# 02_Module.net
KiCad netlist of a schematic drawn in Altium Designer
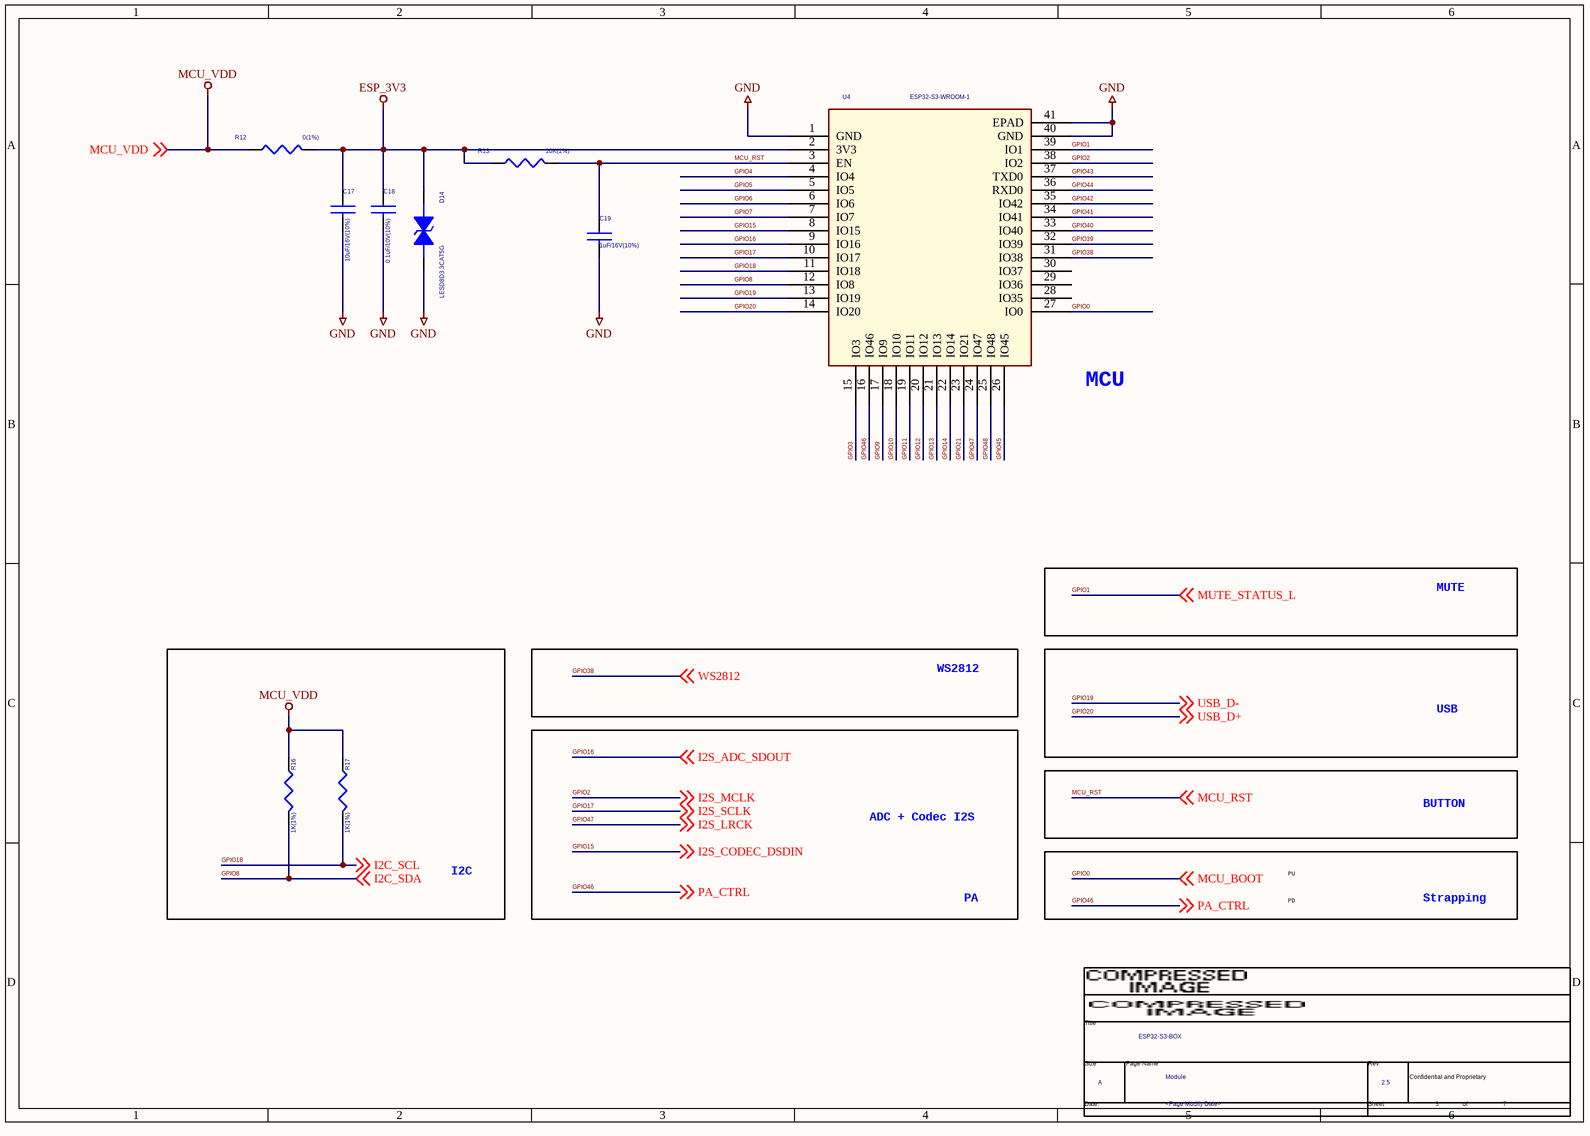
[diagram p0: 02_Module.SchDoc]

(export (version "E")
  (design (tool "Eeschema 10.0.6"))
  (components
    (comp (ref "C17")
      (value "10uF/16V(10%)")
      (footprint "0603_C")
      (fields (field (name "PART NUMBER") "ES11067104600000"))
      (libsource (lib "*") (part "CAPACITOR"))
    )
    (comp (ref "C18")
      (value "0.1uF/10V(10%)")
      (footprint "0402_C")
      (fields (field (name "PART NUMBER") "ES11045103620000"))
      (libsource (lib "*") (part "CAPACITOR"))
    )
    (comp (ref "C19")
      (value "1uF/16V(10%)")
      (footprint "0402_C")
      (fields (field (name "PART NUMBER") "ES11046104610000"))
      (libsource (lib "*") (part "CAPACITOR"))
    )
    (comp (ref "D14")
      (value "LESD8D3.3CAT5G")
      (footprint "SOD-882")
      (fields (field (name "PART NUMBER") "ES31320010000000"))
      (libsource (lib "*") (part "DIODE_BI_DIR"))
    )
    (comp (ref "R12")
      (value "0(1%)")
      (footprint "0603_R")
      (fields (field (name "PART NUMBER") "ES21060000000001"))
      (libsource (lib "*") (part "RESISTOR"))
    )
    (comp (ref "R13")
      (value "10K(1%)")
      (footprint "0402_R")
      (fields (field (name "PART NUMBER") "ES21044100000001"))
      (libsource (lib "*") (part "RESISTOR"))
    )
    (comp (ref "R16")
      (value "1K(1%)")
      (footprint "0201_R")
      (fields (field (name "PART NUMBER") "ES21023100000001"))
      (libsource (lib "*") (part "RESISTOR"))
    )
    (comp (ref "R17")
      (value "1K(1%)")
      (footprint "0201_R")
      (fields (field (name "PART NUMBER") "ES21023100000001"))
      (libsource (lib "*") (part "RESISTOR"))
    )
    (comp (ref "U4")
      (value "ESP32-S3-WROOM-1")
      (footprint "ESP32-S3-WROOM-1")
      (libsource (lib "*") (part "ESP32-S3-WROOM"))
    )
  )
  (nets
    (net (code "1") (name "/GPIO3") (class "Default")
      (node (ref "U4") (pin "15") (pinfunction "IO3_15") (pintype "passive"))
    )
    (net (code "2") (name "/GPIO4") (class "Default")
      (node (ref "U4") (pin "4") (pinfunction "IO4_4") (pintype "passive"))
    )
    (net (code "3") (name "/GPIO5") (class "Default")
      (node (ref "U4") (pin "5") (pinfunction "IO5_5") (pintype "passive"))
    )
    (net (code "4") (name "/GPIO6") (class "Default")
      (node (ref "U4") (pin "6") (pinfunction "IO6_6") (pintype "passive"))
    )
    (net (code "5") (name "/GPIO7") (class "Default")
      (node (ref "U4") (pin "7") (pinfunction "IO7_7") (pintype "passive"))
    )
    (net (code "6") (name "/GPIO9") (class "Default")
      (node (ref "U4") (pin "17") (pinfunction "IO9_17") (pintype "passive"))
    )
    (net (code "7") (name "/GPIO10") (class "Default")
      (node (ref "U4") (pin "18") (pinfunction "IO10_18") (pintype "passive"))
    )
    (net (code "8") (name "/GPIO11") (class "Default")
      (node (ref "U4") (pin "19") (pinfunction "IO11_19") (pintype "passive"))
    )
    (net (code "9") (name "/GPIO12") (class "Default")
      (node (ref "U4") (pin "20") (pinfunction "IO12_20") (pintype "passive"))
    )
    (net (code "10") (name "/GPIO13") (class "Default")
      (node (ref "U4") (pin "21") (pinfunction "IO13_21") (pintype "passive"))
    )
    (net (code "11") (name "/GPIO14") (class "Default")
      (node (ref "U4") (pin "22") (pinfunction "IO14_22") (pintype "passive"))
    )
    (net (code "12") (name "/GPIO21") (class "Default")
      (node (ref "U4") (pin "23") (pinfunction "IO21_23") (pintype "passive"))
    )
    (net (code "13") (name "/GPIO39") (class "Default")
      (node (ref "U4") (pin "32") (pinfunction "IO39_32") (pintype "passive"))
    )
    (net (code "14") (name "/GPIO40") (class "Default")
      (node (ref "U4") (pin "33") (pinfunction "IO40_33") (pintype "passive"))
    )
    (net (code "15") (name "/GPIO41") (class "Default")
      (node (ref "U4") (pin "34") (pinfunction "IO41_34") (pintype "passive"))
    )
    (net (code "16") (name "/GPIO42") (class "Default")
      (node (ref "U4") (pin "35") (pinfunction "IO42_35") (pintype "passive"))
    )
    (net (code "17") (name "/GPIO43") (class "Default")
      (node (ref "U4") (pin "37") (pinfunction "TXD0_37") (pintype "passive"))
    )
    (net (code "18") (name "/GPIO44") (class "Default")
      (node (ref "U4") (pin "36") (pinfunction "RXD0_36") (pintype "passive"))
    )
    (net (code "19") (name "/GPIO45") (class "Default")
      (node (ref "U4") (pin "26") (pinfunction "IO45_26") (pintype "passive"))
    )
    (net (code "20") (name "/GPIO48") (class "Default")
      (node (ref "U4") (pin "25") (pinfunction "IO48_25") (pintype "passive"))
    )
    (net (code "21") (name "ESP_3V3") (class "Default")
      (node (ref "C17") (pin "1") (pinfunction "1_1") (pintype "passive"))
      (node (ref "C18") (pin "1") (pinfunction "1_1") (pintype "passive"))
      (node (ref "D14") (pin "2") (pinfunction "2_2") (pintype "passive"))
      (node (ref "R12") (pin "2") (pinfunction "2_2") (pintype "passive"))
      (node (ref "R13") (pin "1") (pinfunction "1_1") (pintype "passive"))
      (node (ref "U4") (pin "2") (pinfunction "3V3_2") (pintype "power_in"))
    )
    (net (code "22") (name "GND") (class "Default")
      (node (ref "C17") (pin "2") (pinfunction "2_2") (pintype "passive"))
      (node (ref "C18") (pin "2") (pinfunction "2_2") (pintype "passive"))
      (node (ref "C19") (pin "2") (pinfunction "2_2") (pintype "passive"))
      (node (ref "D14") (pin "1") (pinfunction "1_1") (pintype "passive"))
      (node (ref "U4") (pin "1") (pinfunction "GND_1") (pintype "power_in"))
      (node (ref "U4") (pin "40") (pinfunction "GND_40") (pintype "power_in"))
      (node (ref "U4") (pin "41") (pinfunction "EPAD_41") (pintype "power_in"))
    )
    (net (code "23") (name "I2C_SCL") (class "Default")
      (node (ref "R17") (pin "2") (pinfunction "2_2") (pintype "passive"))
      (node (ref "U4") (pin "11") (pinfunction "IO18_11") (pintype "passive"))
    )
    (net (code "24") (name "I2C_SDA") (class "Default")
      (node (ref "R16") (pin "2") (pinfunction "2_2") (pintype "passive"))
      (node (ref "U4") (pin "12") (pinfunction "IO8_12") (pintype "passive"))
    )
    (net (code "25") (name "I2S_ADC_SDOUT") (class "Default")
      (node (ref "U4") (pin "9") (pinfunction "IO16_9") (pintype "passive"))
    )
    (net (code "26") (name "I2S_CODEC_DSDIN") (class "Default")
      (node (ref "U4") (pin "8") (pinfunction "IO15_8") (pintype "passive"))
    )
    (net (code "27") (name "I2S_LRCK") (class "Default")
      (node (ref "U4") (pin "24") (pinfunction "IO47_24") (pintype "passive"))
    )
    (net (code "28") (name "I2S_MCLK") (class "Default")
      (node (ref "U4") (pin "38") (pinfunction "IO2_38") (pintype "passive"))
    )
    (net (code "29") (name "I2S_SCLK") (class "Default")
      (node (ref "U4") (pin "10") (pinfunction "IO17_10") (pintype "passive"))
    )
    (net (code "30") (name "MCU_BOOT") (class "Default")
      (node (ref "U4") (pin "27") (pinfunction "IO0_27") (pintype "passive"))
    )
    (net (code "31") (name "MCU_RST") (class "Default")
      (node (ref "C19") (pin "1") (pinfunction "1_1") (pintype "passive"))
      (node (ref "R13") (pin "2") (pinfunction "2_2") (pintype "passive"))
      (node (ref "U4") (pin "3") (pinfunction "EN_3") (pintype "passive"))
    )
    (net (code "32") (name "MCU_VDD") (class "Default")
      (node (ref "R12") (pin "1") (pinfunction "1_1") (pintype "passive"))
      (node (ref "R16") (pin "1") (pinfunction "1_1") (pintype "passive"))
      (node (ref "R17") (pin "1") (pinfunction "1_1") (pintype "passive"))
    )
    (net (code "33") (name "MUTE_STATUS_L") (class "Default")
      (node (ref "U4") (pin "39") (pinfunction "IO1_39") (pintype "passive"))
    )
    (net (code "34") (name "PA_CTRL") (class "Default")
      (node (ref "U4") (pin "16") (pinfunction "IO46_16") (pintype "passive"))
    )
    (net (code "35") (name "USB_D+") (class "Default")
      (node (ref "U4") (pin "14") (pinfunction "IO20_14") (pintype "passive"))
    )
    (net (code "36") (name "USB_D-") (class "Default")
      (node (ref "U4") (pin "13") (pinfunction "IO19_13") (pintype "passive"))
    )
    (net (code "37") (name "WS2812") (class "Default")
      (node (ref "U4") (pin "31") (pinfunction "IO38_31") (pintype "passive"))
    )
    (net (code "38") (name "unconnected-(U4-IO35-Pad28)") (class "Default")
      (node (ref "U4") (pin "28") (pinfunction "IO35_28") (pintype "passive"))
    )
    (net (code "39") (name "unconnected-(U4-IO36-Pad29)") (class "Default")
      (node (ref "U4") (pin "29") (pinfunction "IO36_29") (pintype "passive"))
    )
    (net (code "40") (name "unconnected-(U4-IO37-Pad30)") (class "Default")
      (node (ref "U4") (pin "30") (pinfunction "IO37_30") (pintype "passive"))
    )
  )
)
